# Power_3V3.net
KiCad netlist of a schematic drawn in Altium Designer
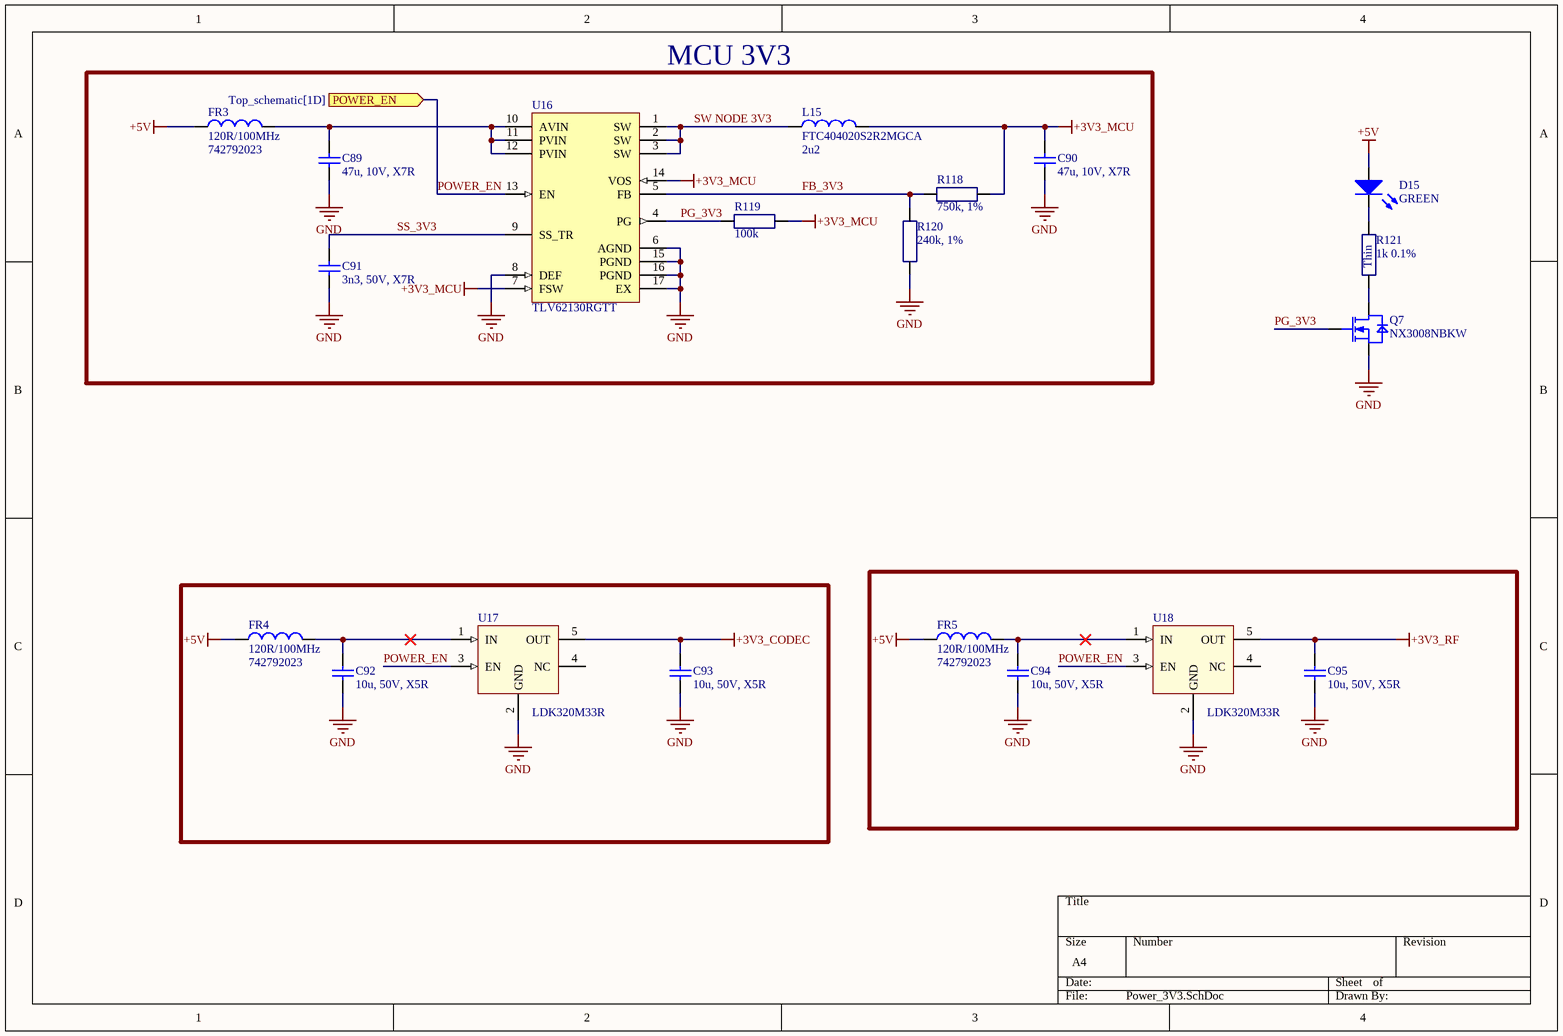
[diagram p0: Power_3V3.SchDoc]

(export (version "E")
  (design (tool "Eeschema 10.0.6"))
  (components
    (comp (ref "C89")
      (value "47u, 10V, X7R")
      (footprint "SMD1210")
      (description "Cap Ceramic 47uF 10V X7R 20% Pad SMD 1210 125C T/R")
      (fields
        (field (name "MANUFACTURER") "Samsung")
        (field (name "MANUFACTURER PART NUMBER") "CL32B476MPJNNNE")
      )
      (libsource (lib "SMD1210Cap") (part "CL32B476MPJNNNE"))
    )
    (comp (ref "C90")
      (value "47u, 10V, X7R")
      (footprint "SMD1210")
      (description "Cap Ceramic 47uF 10V X7R 20% Pad SMD 1210 125C T/R")
      (fields
        (field (name "MANUFACTURER") "Samsung")
        (field (name "MANUFACTURER PART NUMBER") "CL32B476MPJNNNE")
      )
      (libsource (lib "SMD1210Cap") (part "CL32B476MPJNNNE"))
    )
    (comp (ref "C91")
      (value "3n3, 50V, X7R")
      (footprint "SMD0603")
      (description "WALSIN - 0603B332K500CT - CAPACITOR, MLCC, X7R, 3300PF, 50V, 0603")
      (fields
        (field (name "MANUFACTURER") "WALSIN")
        (field (name "MANUFACTURER PART NUMBER") "0603B332K500CT")
      )
      (libsource (lib "SMD0603Cap") (part "0603B332K500CT"))
    )
    (comp (ref "C92")
      (value "10u, 50V, X5R")
      (footprint "SMD1206")
      (description "CAP CER 10UF 50V X5R 1206")
      (fields
        (field (name "MANUFACTURER") "Taiyo Yuden")
        (field (name "MANUFACTURER PART NUMBER") "UMK316BBJ106KL-T")
      )
      (libsource (lib "SMD1206Cap") (part "UMK316BBJ106KL-T"))
    )
    (comp (ref "C93")
      (value "10u, 50V, X5R")
      (footprint "SMD1206")
      (description "CAP CER 10UF 50V X5R 1206")
      (fields
        (field (name "MANUFACTURER") "Taiyo Yuden")
        (field (name "MANUFACTURER PART NUMBER") "UMK316BBJ106KL-T")
      )
      (libsource (lib "SMD1206Cap") (part "UMK316BBJ106KL-T"))
    )
    (comp (ref "C94")
      (value "10u, 50V, X5R")
      (footprint "SMD1206")
      (description "CAP CER 10UF 50V X5R 1206")
      (fields
        (field (name "MANUFACTURER") "Taiyo Yuden")
        (field (name "MANUFACTURER PART NUMBER") "UMK316BBJ106KL-T")
      )
      (libsource (lib "SMD1206Cap") (part "UMK316BBJ106KL-T"))
    )
    (comp (ref "C95")
      (value "10u, 50V, X5R")
      (footprint "SMD1206")
      (description "CAP CER 10UF 50V X5R 1206")
      (fields
        (field (name "MANUFACTURER") "Taiyo Yuden")
        (field (name "MANUFACTURER PART NUMBER") "UMK316BBJ106KL-T")
      )
      (libsource (lib "SMD1206Cap") (part "UMK316BBJ106KL-T"))
    )
    (comp (ref "D15")
      (value "GREEN")
      (footprint "MCL-S270")
      (description "MULTICOMP - MCL-S270GC - LED, 0805, GREEN, 10MCD, 570NM")
      (fields
        (field (name "MANUFACTURER") "MULTICOMP")
        (field (name "MANUFACTURER PART NUMBER") "MCL-S270GC")
      )
      (libsource (lib "Diodes") (part "MCL-S270GC"))
    )
    (comp (ref "FR3")
      (value "120R/100MHz")
      (footprint "SMD0805 - R")
      (description "WURTH ELEKTRONIK - 742792023 - FERRITE BEAD, 0.03OHM, 3A, 0805")
      (fields
        (field (name "MANUFACTURER") "WURTH ELEKTRONIK")
        (field (name "MANUFACTURER PART NUMBER") "742792023")
      )
      (libsource (lib "Inductors") (part "742792023"))
    )
    (comp (ref "FR4")
      (value "120R/100MHz")
      (footprint "SMD0805 - R")
      (description "WURTH ELEKTRONIK - 742792023 - FERRITE BEAD, 0.03OHM, 3A, 0805")
      (fields
        (field (name "MANUFACTURER") "WURTH ELEKTRONIK")
        (field (name "MANUFACTURER PART NUMBER") "742792023")
      )
      (libsource (lib "Inductors") (part "742792023"))
    )
    (comp (ref "FR5")
      (value "120R/100MHz")
      (footprint "SMD0805 - R")
      (description "WURTH ELEKTRONIK - 742792023 - FERRITE BEAD, 0.03OHM, 3A, 0805")
      (fields
        (field (name "MANUFACTURER") "WURTH ELEKTRONIK")
        (field (name "MANUFACTURER PART NUMBER") "742792023")
      )
      (libsource (lib "Inductors") (part "742792023"))
    )
    (comp (ref "L15")
      (value "FTC404020S2R2MGCA")
      (footprint "FTC404020S")
      (description "FIXED IND 2.2uH 5.5A 36mΩ SMD,4.1x4.1mm")
      (fields (field (name "MANUFACTURER") "Cjiang") (field (name "INDUCTANCE") "2u2"))
      (libsource (lib "Inductors") (part "FTC404020S2R2MGCA"))
    )
    (comp (ref "Q7")
      (value "NX3008NBKW")
      (footprint "SOT323")
      (description "NXP - NX3008NBKW - MOSFET, N CH, 30V, 350MA, SOT323")
      (fields (field (name "MANUFACTURER") "NXP"))
      (libsource (lib "Transistors") (part "NX3008NBKW"))
    )
    (comp (ref "R118")
      (value "750k, 1%")
      (footprint "SMD0603 - R")
      (description "RES SMD 750K OHM 1% 1/10W 0603")
      (fields
        (field (name "MANUFACTURER") "Yageo")
        (field (name "MANUFACTURER PART NUMBER") "RC0603FR-07750KL")
      )
      (libsource (lib "SMD0603Res") (part "RC0603FR-07750KL"))
    )
    (comp (ref "R119")
      (value "100k")
      (footprint "SMD0402 - R")
      (description "62.5mW Thick Film Resistors 50V ±100ppm/℃ ±1% 100kΩ 0402 Chip Resistor - Surface Mount ROHS")
      (fields
        (field (name "MANUFACTURER") "Yageo Group")
        (field (name "MANUFACTURER PART NUMBER") "RC0402FR-07100KL")
      )
      (libsource (lib "SMD0402Res") (part "RC0402FR-07100KL"))
    )
    (comp (ref "R120")
      (value "240k, 1%")
      (footprint "SMD0603 - R")
      (description "RES SMD 240K OHM 1% 1/10W 0603")
      (fields
        (field (name "MANUFACTURER") "Vishay")
        (field (name "MANUFACTURER PART NUMBER") "CRCW0603240KFKEA")
      )
      (libsource (lib "SMD0603Res") (part "CRCW0603240KFKEA"))
    )
    (comp (ref "R121")
      (value "1k 0.1%")
      (footprint "SMD0402 - R")
      (description "62.5mW Thin Film Resistor 25V ±25ppm/℃ ±0.1% 1kΩ 0402 Chip Resistor - Surface Mount ROHS")
      (fields
        (field (name "MANUFACTURER") "Uniroyal")
        (field (name "MANUFACTURER PART NUMBER") "TC0225B1001TCC")
      )
      (libsource (lib "SMD0402ResThin") (part "TC0225B1001TCC"))
    )
    (comp (ref "U16")
      (value "TLV62130RGTT")
      (footprint "QFN50P300X300X80_HS-17M")
      (description "TEXAS INSTRUMENTS - TLV62130RGTT - DC-DC CONV, BUCK, 2.5MHZ, QFN-16")
      (fields (field (name "MANUFACTURER") "TEXAS INSTRUMENTS"))
      (libsource (lib "Lib1") (part "TLV62130RGTT"))
    )
    (comp (ref "U17")
      (value "LDK320M33R")
      (footprint "SOT23-5")
      (description "IC REG LINEAR 200MA SOT23-5")
      (fields (field (name "MANUFACTURER") "STMicroelectronics"))
      (libsource (lib "Lib1") (part "LDK320M33R"))
    )
    (comp (ref "U18")
      (value "LDK320M33R")
      (footprint "SOT23-5")
      (description "IC REG LINEAR 200MA SOT23-5")
      (fields (field (name "MANUFACTURER") "STMicroelectronics"))
      (libsource (lib "Lib1") (part "LDK320M33R"))
    )
  )
  (nets
    (net (code "1") (name "+3V3_CODEC") (class "Default")
      (node (ref "C93") (pin "2") (pinfunction "2_2") (pintype "passive"))
      (node (ref "U17") (pin "5") (pinfunction "OUT_5") (pintype "power_in"))
    )
    (net (code "2") (name "+3V3_MCU") (class "Default")
      (node (ref "C90") (pin "2") (pinfunction "2_2") (pintype "passive"))
      (node (ref "L15") (pin "2") (pinfunction "2_2") (pintype "passive"))
      (node (ref "R118") (pin "2") (pinfunction "2_2") (pintype "passive"))
      (node (ref "R119") (pin "2") (pinfunction "2_2") (pintype "passive"))
      (node (ref "U16") (pin "14") (pinfunction "VOS_14") (pintype "input"))
      (node (ref "U16") (pin "7") (pinfunction "FSW_7") (pintype "input"))
    )
    (net (code "3") (name "+3V3_RF") (class "Default")
      (node (ref "C95") (pin "2") (pinfunction "2_2") (pintype "passive"))
      (node (ref "U18") (pin "5") (pinfunction "OUT_5") (pintype "power_in"))
    )
    (net (code "4") (name "+5V") (class "Default")
      (node (ref "D15") (pin "1") (pinfunction "A_1") (pintype "passive"))
      (node (ref "FR3") (pin "1") (pinfunction "1_1") (pintype "passive"))
      (node (ref "FR4") (pin "1") (pinfunction "1_1") (pintype "passive"))
      (node (ref "FR5") (pin "1") (pinfunction "1_1") (pintype "passive"))
    )
    (net (code "5") (name "/FB_3V3") (class "Default")
      (node (ref "R118") (pin "1") (pinfunction "1_1") (pintype "passive"))
      (node (ref "R120") (pin "2") (pinfunction "2_2") (pintype "passive"))
      (node (ref "U16") (pin "5") (pinfunction "FB_5") (pintype "passive"))
    )
    (net (code "6") (name "/PG_3V3") (class "Default")
      (node (ref "Q7") (pin "1") (pinfunction "G_1") (pintype "passive"))
      (node (ref "R119") (pin "1") (pinfunction "1_1") (pintype "passive"))
      (node (ref "U16") (pin "4") (pinfunction "PG_4") (pintype "output"))
    )
    (net (code "7") (name "/POWER_EN") (class "Default")
      (node (ref "U16") (pin "13") (pinfunction "EN_13") (pintype "input"))
      (node (ref "U17") (pin "3") (pinfunction "EN_3") (pintype "input"))
      (node (ref "U18") (pin "3") (pinfunction "EN_3") (pintype "input"))
    )
    (net (code "8") (name "/SS_3V3") (class "Default")
      (node (ref "C91") (pin "2") (pinfunction "2_2") (pintype "passive"))
      (node (ref "U16") (pin "9") (pinfunction "SS_TR_9") (pintype "passive"))
    )
    (net (code "9") (name "/SW NODE 3V3") (class "Default")
      (node (ref "L15") (pin "1") (pinfunction "1_1") (pintype "passive"))
      (node (ref "U16") (pin "1") (pinfunction "SW_1") (pintype "passive"))
      (node (ref "U16") (pin "2") (pinfunction "SW_2") (pintype "passive"))
      (node (ref "U16") (pin "3") (pinfunction "SW_3") (pintype "passive"))
    )
    (net (code "10") (name "GND") (class "Default")
      (node (ref "C89") (pin "1") (pinfunction "1_1") (pintype "passive"))
      (node (ref "C90") (pin "1") (pinfunction "1_1") (pintype "passive"))
      (node (ref "C91") (pin "1") (pinfunction "1_1") (pintype "passive"))
      (node (ref "C92") (pin "1") (pinfunction "1_1") (pintype "passive"))
      (node (ref "C93") (pin "1") (pinfunction "1_1") (pintype "passive"))
      (node (ref "C94") (pin "1") (pinfunction "1_1") (pintype "passive"))
      (node (ref "C95") (pin "1") (pinfunction "1_1") (pintype "passive"))
      (node (ref "Q7") (pin "2") (pinfunction "S_2") (pintype "passive"))
      (node (ref "R120") (pin "1") (pinfunction "1_1") (pintype "passive"))
      (node (ref "U16") (pin "15") (pinfunction "PGND_15") (pintype "power_in"))
      (node (ref "U16") (pin "16") (pinfunction "PGND_16") (pintype "power_in"))
      (node (ref "U16") (pin "17") (pinfunction "EX_17") (pintype "power_in"))
      (node (ref "U16") (pin "6") (pinfunction "AGND_6") (pintype "power_in"))
      (node (ref "U16") (pin "8") (pinfunction "DEF_8") (pintype "input"))
      (node (ref "U17") (pin "2") (pinfunction "GND_2") (pintype "power_in"))
      (node (ref "U18") (pin "2") (pinfunction "GND_2") (pintype "power_in"))
    )
    (net (code "11") (name "Net-(D15-K)") (class "Default")
      (node (ref "D15") (pin "2") (pinfunction "K_2") (pintype "passive"))
      (node (ref "R121") (pin "2") (pinfunction "2_2") (pintype "passive"))
    )
    (net (code "12") (name "Net-(Q7-D)") (class "Default")
      (node (ref "Q7") (pin "3") (pinfunction "D_3") (pintype "passive"))
      (node (ref "R121") (pin "1") (pinfunction "1_1") (pintype "passive"))
    )
    (net (code "13") (name "Net-(U16-AVIN)") (class "Default")
      (node (ref "C89") (pin "2") (pinfunction "2_2") (pintype "passive"))
      (node (ref "FR3") (pin "2") (pinfunction "2_2") (pintype "passive"))
      (node (ref "U16") (pin "10") (pinfunction "AVIN_10") (pintype "power_in"))
      (node (ref "U16") (pin "11") (pinfunction "PVIN_11") (pintype "power_in"))
      (node (ref "U16") (pin "12") (pinfunction "PVIN_12") (pintype "power_in"))
    )
    (net (code "14") (name "Net-(U17-IN)") (class "Default")
      (node (ref "C92") (pin "2") (pinfunction "2_2") (pintype "passive"))
      (node (ref "FR4") (pin "2") (pinfunction "2_2") (pintype "passive"))
      (node (ref "U17") (pin "1") (pinfunction "IN_1") (pintype "input"))
    )
    (net (code "15") (name "Net-(U18-IN)") (class "Default")
      (node (ref "C94") (pin "2") (pinfunction "2_2") (pintype "passive"))
      (node (ref "FR5") (pin "2") (pinfunction "2_2") (pintype "passive"))
      (node (ref "U18") (pin "1") (pinfunction "IN_1") (pintype "input"))
    )
    (net (code "16") (name "unconnected-(U17-NC-Pad4)") (class "Default")
      (node (ref "U17") (pin "4") (pinfunction "NC_4") (pintype "passive"))
    )
    (net (code "17") (name "unconnected-(U18-NC-Pad4)") (class "Default")
      (node (ref "U18") (pin "4") (pinfunction "NC_4") (pintype "passive"))
    )
  )
)
